# 04_-CH340.net
KiCad netlist of a schematic drawn in Altium Designer
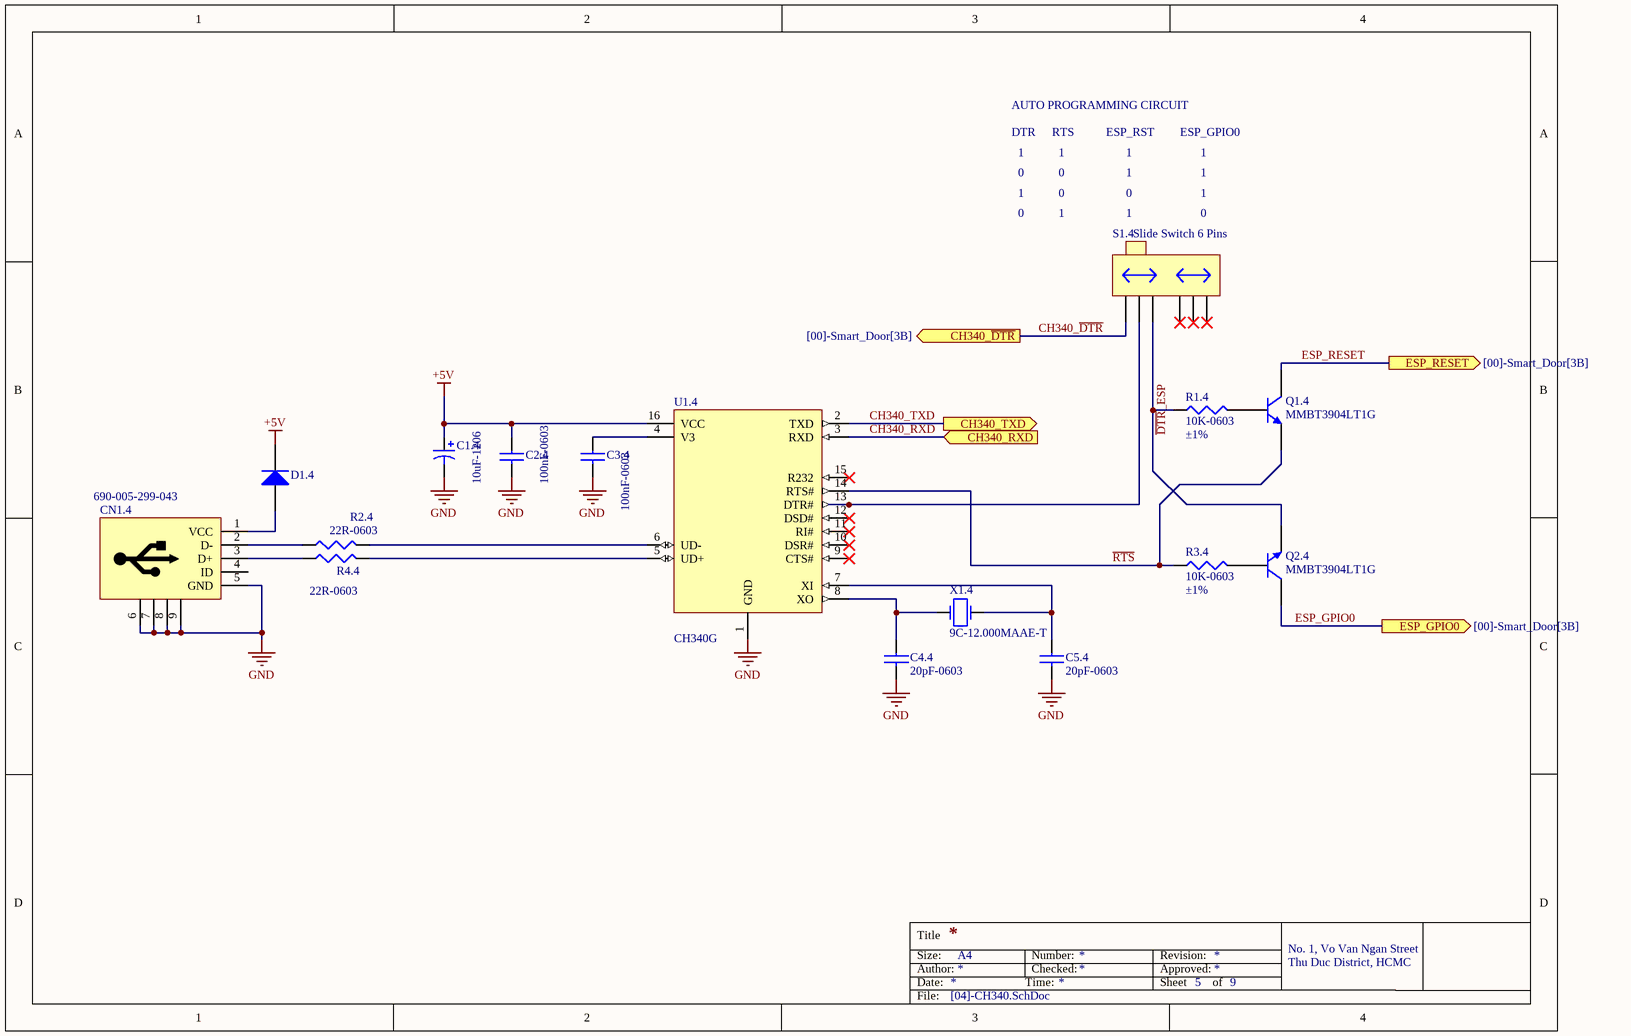
[diagram p0: [04]-CH340.SchDoc]

(export (version "E")
  (design (tool "Eeschema 10.0.6"))
  (components
    (comp (ref "C1.4")
      (value "10uF-1206")
      (footprint "CAP1206_TANTALUM_YELLOW")
      (description "CAP TANT 10UF 16V 10% 1206")
      (fields (field (name "TOLERANCE") "±10%"))
      (libsource (lib "Indruino") (part "T491A106K016AT"))
    )
    (comp (ref "C2.4")
      (value "100nF-0603")
      (footprint "CAP0603")
      (description "CAP CER 0.1UF 100V X7R 0603")
      (fields
        (field (name "MANUFACTURER") "Yageo")
        (field (name "MANUFACTURER PART NUMBER") "CC0603KRX7R0BB104")
      )
      (libsource (lib "Indruino") (part "CC0603KRX7R0BB104"))
    )
    (comp (ref "C3.4")
      (value "100nF-0603")
      (footprint "CAP0603")
      (description "CAP CER 0.1UF 100V X7R 0603")
      (fields
        (field (name "MANUFACTURER") "Yageo")
        (field (name "MANUFACTURER PART NUMBER") "CC0603KRX7R0BB104")
      )
      (libsource (lib "Indruino") (part "CC0603KRX7R0BB104"))
    )
    (comp (ref "C4.4")
      (value "20pF-0603")
      (footprint "CAP0603")
      (description "CAP CER 20PF 50V C0G/NPO 0603")
      (fields (field (name "TOLERANCE") "±5%"))
      (libsource (lib "Indruino") (part "CC0603JRNPO9BN200"))
    )
    (comp (ref "C5.4")
      (value "20pF-0603")
      (footprint "CAP0603")
      (description "CAP CER 20PF 50V C0G/NPO 0603")
      (fields (field (name "TOLERANCE") "±5%"))
      (libsource (lib "Indruino") (part "CC0603JRNPO9BN200"))
    )
    (comp (ref "CN1.4")
      (value "690-005-299-043")
      (footprint "USB-B-MINI_690-005-299-043")
      (description "CONN MINI USB RCPT RA TYPE B SMD")
      (fields (field (name "MANUFACTURER") "EDAC Inc."))
      (libsource (lib "Indruino") (part "USB_690-005-299-043"))
    )
    (comp (ref "D1.4")
      (value "DIODE_S1A-13-F")
      (footprint "DO-214AC")
      (description "DIODE GEN PURP 50V 1A SMA")
      (fields
        (field (name "MANUFACTURER") "Diodes Incorporated")
        (field (name "MANUFACTURER PART NUMBER") "S1A-13-F")
      )
      (libsource (lib "Indruino") (part "DIODE_S1A-13-F"))
    )
    (comp (ref "Q1.4")
      (value "MMBT3904LT1G")
      (footprint "Indruino:SOT23-3")
      (description "TRANS NPN 40V 0.2A SOT23")
      (libsource (lib "Indruino") (part "MMBT3904LT1G"))
    )
    (comp (ref "Q2.4")
      (value "MMBT3904LT1G")
      (footprint "Indruino:SOT23-3")
      (description "TRANS NPN 40V 0.2A SOT23")
      (libsource (lib "Indruino") (part "MMBT3904LT1G"))
    )
    (comp (ref "R1.4")
      (value "10K-0603")
      (footprint "RES0603")
      (description "RES SMD 10K OHM 1% 1/10W 0603")
      (fields
        (field (name "MANUFACTURER") "Yageo")
        (field (name "MANUFACTURER PART NUMBER") "RC0603FR-0710KL")
        (field (name "TOLERANCE") "±1%")
      )
      (libsource (lib "Indruino") (part "RC0603FR-0710KL"))
    )
    (comp (ref "R2.4")
      (value "22R-0603")
      (footprint "RES0603")
      (description "RES SMD 22 OHM 5% 1/10W 0603")
      (fields (field (name "TOLERANCE") "±5%"))
      (libsource (lib "Indruino") (part "RC0603JR-0722RL"))
    )
    (comp (ref "R3.4")
      (value "10K-0603")
      (footprint "RES0603")
      (description "RES SMD 10K OHM 1% 1/10W 0603")
      (fields
        (field (name "MANUFACTURER") "Yageo")
        (field (name "MANUFACTURER PART NUMBER") "RC0603FR-0710KL")
        (field (name "TOLERANCE") "±1%")
      )
      (libsource (lib "Indruino") (part "RC0603FR-0710KL"))
    )
    (comp (ref "R4.4")
      (value "22R-0603")
      (footprint "RES0603")
      (description "RES SMD 22 OHM 5% 1/10W 0603")
      (fields (field (name "TOLERANCE") "±5%"))
      (libsource (lib "Indruino") (part "RC0603JR-0722RL"))
    )
    (comp (ref "S1.4")
      (value "Slide Switch 6 Pins")
      (footprint "MinhTien_PCBLib:SW6_MSS-22D18")
      (description "Switch")
      (fields (field (name "PUBLISHER") "Altium Limited"))
      (libsource (lib "MinhTien_SCHLib") (part "Slide Switch 6 Pins"))
    )
    (comp (ref "U1.4")
      (value "CH340G")
      (footprint "AZ_Lib:CH340G")
      (description "USB to serial chip CH340")
      (libsource (lib "AZ_Lib") (part "CH340G"))
    )
    (comp (ref "X1.4")
      (value "9C-12.000MAAE-T")
      (footprint "XTAL_SMD_HC-49S")
      (description "CRYSTAL 12.0000MHZ 12PF SMD")
      (fields (field (name "MANUFACTURER") "TXC CORPORATION"))
      (libsource (lib "Indruino") (part "XTAL_9C-12.000MAAE-T"))
    )
  )
  (nets
    (net (code "1") (name "+5V") (class "Default")
      (node (ref "C1.4") (pin "1") (pinfunction "1_1") (pintype "passive"))
      (node (ref "C2.4") (pin "1") (pinfunction "1_1") (pintype "passive"))
      (node (ref "D1.4") (pin "2") (pinfunction "K_2") (pintype "passive"))
      (node (ref "U1.4") (pin "16") (pinfunction "VCC_16") (pintype "power_in"))
    )
    (net (code "2") (name "/CH340_RXD") (class "Default")
      (node (ref "U1.4") (pin "3") (pinfunction "RXD_3") (pintype "input"))
    )
    (net (code "3") (name "/CH340_TXD") (class "Default")
      (node (ref "U1.4") (pin "2") (pinfunction "TXD_2") (pintype "output"))
    )
    (net (code "4") (name "/CH340_~{DTR}") (class "Default")
      (node (ref "S1.4") (pin "1") (pinfunction "NC_1") (pintype "passive"))
    )
    (net (code "5") (name "/ESP_GPIO0") (class "Default")
      (node (ref "Q2.4") (pin "3") (pinfunction "C_3") (pintype "passive"))
    )
    (net (code "6") (name "/ESP_RESET") (class "Default")
      (node (ref "Q1.4") (pin "3") (pinfunction "C_3") (pintype "passive"))
    )
    (net (code "7") (name "/~{DTR}_ESP") (class "Default")
      (node (ref "Q2.4") (pin "2") (pinfunction "E_2") (pintype "passive"))
      (node (ref "R1.4") (pin "1") (pinfunction "1_1") (pintype "passive"))
      (node (ref "S1.4") (pin "5") (pinfunction "NO_5") (pintype "passive"))
    )
    (net (code "8") (name "/~{RTS}") (class "Default")
      (node (ref "Q1.4") (pin "2") (pinfunction "E_2") (pintype "passive"))
      (node (ref "R3.4") (pin "1") (pinfunction "1_1") (pintype "passive"))
      (node (ref "U1.4") (pin "14") (pinfunction "RTS#_14") (pintype "output"))
    )
    (net (code "9") (name "GND") (class "Default")
      (node (ref "C1.4") (pin "2") (pinfunction "2_2") (pintype "passive"))
      (node (ref "C2.4") (pin "2") (pinfunction "2_2") (pintype "passive"))
      (node (ref "C3.4") (pin "2") (pinfunction "2_2") (pintype "passive"))
      (node (ref "C4.4") (pin "2") (pinfunction "2_2") (pintype "passive"))
      (node (ref "C5.4") (pin "2") (pinfunction "2_2") (pintype "passive"))
      (node (ref "CN1.4") (pin "5") (pinfunction "GND_5") (pintype "passive"))
      (node (ref "CN1.4") (pin "6") (pinfunction "6_6") (pintype "power_in"))
      (node (ref "CN1.4") (pin "7") (pinfunction "7_7") (pintype "power_in"))
      (node (ref "CN1.4") (pin "8") (pinfunction "8_8") (pintype "power_in"))
      (node (ref "CN1.4") (pin "9") (pinfunction "9_9") (pintype "power_in"))
      (node (ref "U1.4") (pin "1") (pinfunction "GND_1") (pintype "power_in"))
    )
    (net (code "10") (name "Net-(CN1.4-D+)") (class "Default")
      (node (ref "CN1.4") (pin "3") (pinfunction "D+_3") (pintype "passive"))
      (node (ref "R4.4") (pin "1") (pinfunction "1_1") (pintype "passive"))
    )
    (net (code "11") (name "Net-(CN1.4-D-)") (class "Default")
      (node (ref "CN1.4") (pin "2") (pinfunction "D-_2") (pintype "passive"))
      (node (ref "R2.4") (pin "1") (pinfunction "1_1") (pintype "passive"))
    )
    (net (code "12") (name "Net-(CN1.4-VCC)") (class "Default")
      (node (ref "CN1.4") (pin "1") (pinfunction "VCC_1") (pintype "passive"))
      (node (ref "D1.4") (pin "1") (pinfunction "A_1") (pintype "passive"))
    )
    (net (code "13") (name "Net-(Q1.4-B)") (class "Default")
      (node (ref "Q1.4") (pin "1") (pinfunction "B_1") (pintype "passive"))
      (node (ref "R1.4") (pin "2") (pinfunction "2_2") (pintype "passive"))
    )
    (net (code "14") (name "Net-(Q2.4-B)") (class "Default")
      (node (ref "Q2.4") (pin "1") (pinfunction "B_1") (pintype "passive"))
      (node (ref "R3.4") (pin "2") (pinfunction "2_2") (pintype "passive"))
    )
    (net (code "15") (name "Net-(U1.4-DTR#)") (class "Default")
      (node (ref "S1.4") (pin "3") (pinfunction "COM_3") (pintype "passive"))
      (node (ref "U1.4") (pin "13") (pinfunction "DTR#_13") (pintype "output"))
    )
    (net (code "16") (name "Net-(U1.4-UD+)") (class "Default")
      (node (ref "R4.4") (pin "2") (pinfunction "2_2") (pintype "passive"))
      (node (ref "U1.4") (pin "5") (pinfunction "UD+_5") (pintype "bidirectional"))
    )
    (net (code "17") (name "Net-(U1.4-UD-)") (class "Default")
      (node (ref "R2.4") (pin "2") (pinfunction "2_2") (pintype "passive"))
      (node (ref "U1.4") (pin "6") (pinfunction "UD-_6") (pintype "bidirectional"))
    )
    (net (code "18") (name "Net-(U1.4-V3)") (class "Default")
      (node (ref "C3.4") (pin "1") (pinfunction "1_1") (pintype "passive"))
      (node (ref "U1.4") (pin "4") (pinfunction "V3_4") (pintype "power_in"))
    )
    (net (code "19") (name "Net-(U1.4-XI)") (class "Default")
      (node (ref "C5.4") (pin "1") (pinfunction "1_1") (pintype "passive"))
      (node (ref "U1.4") (pin "7") (pinfunction "XI_7") (pintype "input"))
      (node (ref "X1.4") (pin "1") (pinfunction "OSC1_1") (pintype "passive"))
    )
    (net (code "20") (name "Net-(U1.4-XO)") (class "Default")
      (node (ref "C4.4") (pin "1") (pinfunction "1_1") (pintype "passive"))
      (node (ref "U1.4") (pin "8") (pinfunction "XO_8") (pintype "output"))
      (node (ref "X1.4") (pin "2") (pinfunction "OSC2_2") (pintype "passive"))
    )
    (net (code "21") (name "unconnected-(CN1.4-ID-Pad4)") (class "Default")
      (node (ref "CN1.4") (pin "4") (pinfunction "ID_4") (pintype "passive"))
    )
    (net (code "22") (name "unconnected-(S1.4-COM-Pad4)") (class "Default")
      (node (ref "S1.4") (pin "4") (pinfunction "COM_4") (pintype "passive+no_connect"))
    )
    (net (code "23") (name "unconnected-(S1.4-NC-Pad2)") (class "Default")
      (node (ref "S1.4") (pin "2") (pinfunction "NC_2") (pintype "passive+no_connect"))
    )
    (net (code "24") (name "unconnected-(S1.4-NO-Pad6)") (class "Default")
      (node (ref "S1.4") (pin "6") (pinfunction "NO_6") (pintype "passive+no_connect"))
    )
    (net (code "25") (name "unconnected-(U1.4-CTS#-Pad9)") (class "Default")
      (node (ref "U1.4") (pin "9") (pinfunction "CTS#_9") (pintype "input+no_connect"))
    )
    (net (code "26") (name "unconnected-(U1.4-DSD#-Pad12)") (class "Default")
      (node (ref "U1.4") (pin "12") (pinfunction "DSD#_12") (pintype "input+no_connect"))
    )
    (net (code "27") (name "unconnected-(U1.4-DSR#-Pad10)") (class "Default")
      (node (ref "U1.4") (pin "10") (pinfunction "DSR#_10") (pintype "input+no_connect"))
    )
    (net (code "28") (name "unconnected-(U1.4-R232-Pad15)") (class "Default")
      (node (ref "U1.4") (pin "15") (pinfunction "R232_15") (pintype "input+no_connect"))
    )
    (net (code "29") (name "unconnected-(U1.4-RI#-Pad11)") (class "Default")
      (node (ref "U1.4") (pin "11") (pinfunction "RI#_11") (pintype "input+no_connect"))
    )
  )
)
